# -20210715.net
KiCad netlist of a schematic drawn in Altium Designer
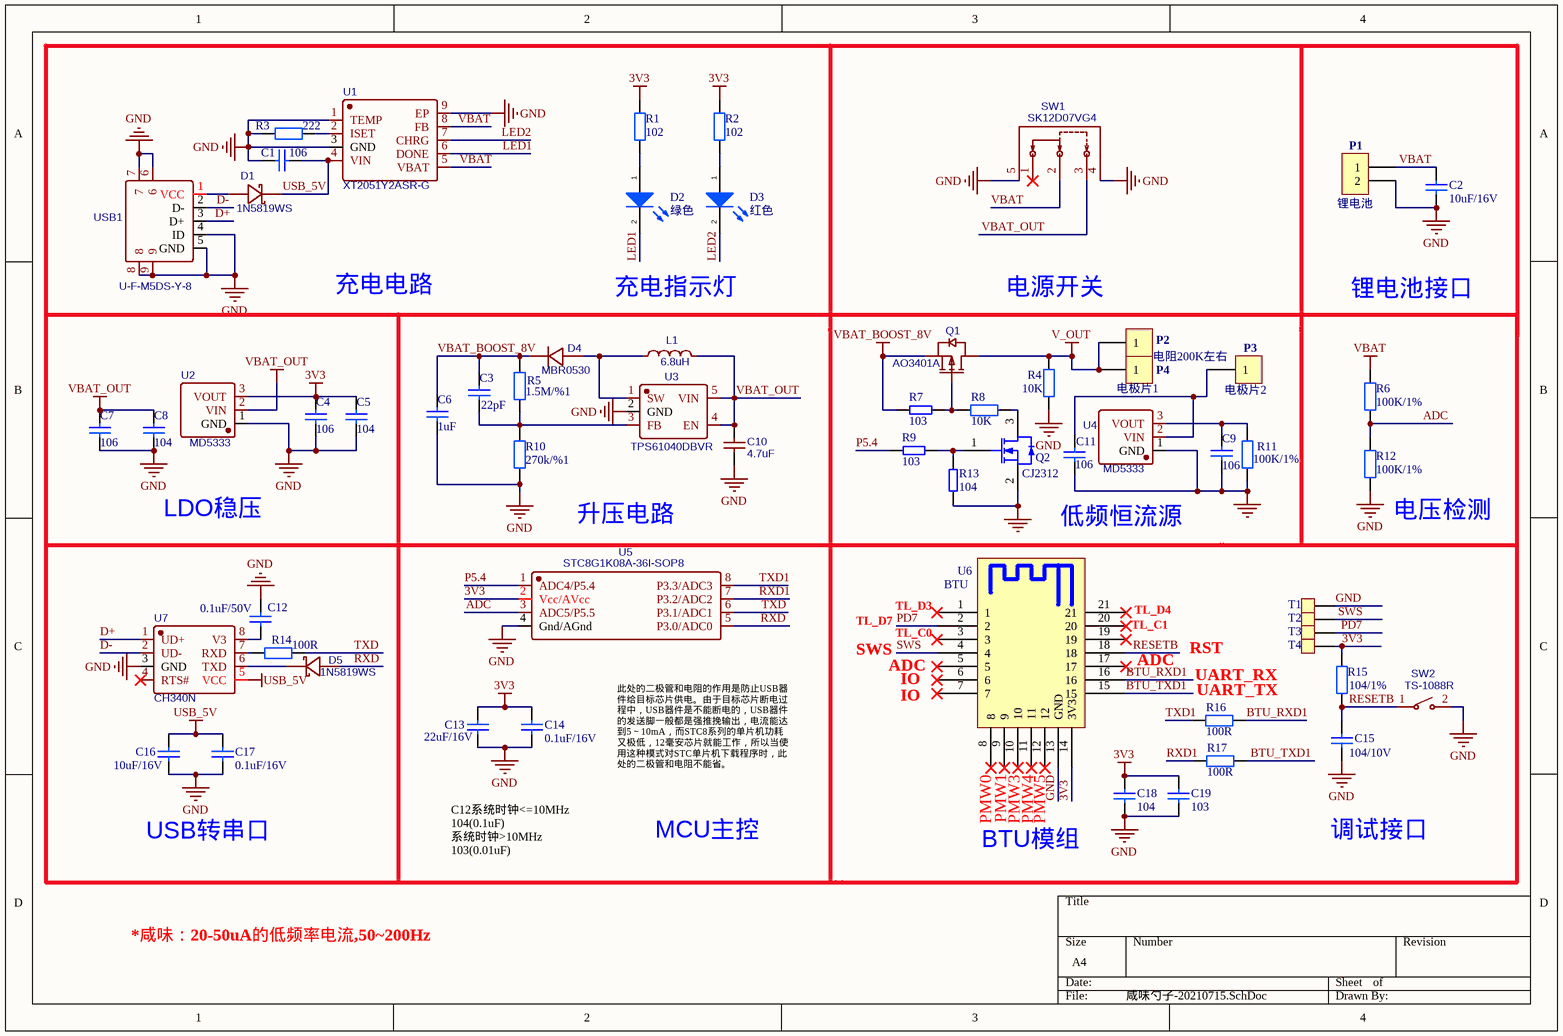
[diagram p0: 咸味勺子-20210715.SchDoc]

(export (version "E")
  (design (tool "Eeschema 10.0.6"))
  (components
    (comp (ref "C1")
      (value "106")
      (footprint "C0603")
      (description "无极性电容")
      (fields (field (name "PART NUMBER") "1.02.03.00181") (field (name "修改人") "system"))
      (libsource (lib "Database_Libs") (part "Capacitor - non polarized"))
    )
    (comp (ref "C2")
      (value "10uF/16V")
      (footprint "C0603")
      (description "无极性电容")
      (fields (field (name "PART NUMBER") "1.02.05.00869"))
      (libsource (lib "Database_Libs4") (part "Capacitor - non polarized"))
    )
    (comp (ref "C3")
      (value "22pF")
      (footprint "C0402_GRM15")
      (description "无极性电容")
      (fields (field (name "PART NUMBER") "1.02.05.00869"))
      (libsource (lib "Database_Libs4") (part "Capacitor - non polarized"))
    )
    (comp (ref "C4")
      (value "106")
      (footprint "C0603")
      (description "无极性电容")
      (fields (field (name "PART NUMBER") "1.02.05.00869"))
      (libsource (lib "Database_Libs4") (part "Capacitor - non polarized"))
    )
    (comp (ref "C5")
      (value "104")
      (footprint "C0402_GRM15")
      (description "无极性电容")
      (fields (field (name "PART NUMBER") "1.02.05.00869"))
      (libsource (lib "Database_Libs4") (part "Capacitor - non polarized"))
    )
    (comp (ref "C6")
      (value "1uF")
      (footprint "C0603")
      (description "无极性电容")
      (fields (field (name "PART NUMBER") "1.02.05.00869"))
      (libsource (lib "Database_Libs4") (part "Capacitor - non polarized"))
    )
    (comp (ref "C7")
      (value "106")
      (footprint "C0603")
      (description "无极性电容")
      (fields (field (name "PART NUMBER") "1.02.05.00869"))
      (libsource (lib "Database_Libs4") (part "Capacitor - non polarized"))
    )
    (comp (ref "C8")
      (value "104")
      (footprint "C0402_GRM15")
      (description "无极性电容")
      (fields (field (name "PART NUMBER") "1.02.05.00869"))
      (libsource (lib "Database_Libs4") (part "Capacitor - non polarized"))
    )
    (comp (ref "C9")
      (value "106")
      (footprint "C0603")
      (description "无极性电容")
      (fields (field (name "PART NUMBER") "1.02.05.00869"))
      (libsource (lib "Database_Libs4") (part "Capacitor - non polarized"))
    )
    (comp (ref "C10")
      (value "4.7uF")
      (footprint "JMK212BJ475KG-T")
      (fields
        (field (name "BOM_MANUFACTURER PART") "JMK212BJ475KG-T")
        (field (name "BOM_SUPPLIER PART") "C92788")
      )
      (libsource (lib "altium-import") (part "root_1_4.7uF_"))
    )
    (comp (ref "C11")
      (value "106")
      (footprint "C0603")
      (description "无极性电容")
      (fields (field (name "PART NUMBER") "1.02.05.00869"))
      (libsource (lib "Database_Libs4") (part "Capacitor - non polarized"))
    )
    (comp (ref "C12")
      (value "0.1uF/50V")
      (footprint "C0402_GRM15")
      (description "无极性电容")
      (fields (field (name "PART NUMBER") "1.02.05.00834") (field (name "修改人") "system"))
      (libsource (lib "Database_Libs") (part "Capacitor - non polarized"))
    )
    (comp (ref "C13")
      (value "22uF/16V")
      (footprint "C0603")
      (description "无极性电容")
      (fields (field (name "PART NUMBER") "1.02.03.00181") (field (name "修改人") "system"))
      (libsource (lib "Database_Libs") (part "Capacitor - non polarized"))
    )
    (comp (ref "C14")
      (value "0.1uF/16V")
      (footprint "C0402_GRM15")
      (description "无极性电容")
      (fields (field (name "PART NUMBER") "1.02.05.00834") (field (name "修改人") "system"))
      (libsource (lib "Database_Libs") (part "Capacitor - non polarized"))
    )
    (comp (ref "C15")
      (value "104/10V")
      (footprint "C0402_GRM15")
      (description "无极性电容")
      (fields (field (name "PART NUMBER") "1.02.05.00869"))
      (libsource (lib "Database_Libs4") (part "Capacitor - non polarized"))
    )
    (comp (ref "C16")
      (value "10uF/16V")
      (footprint "C0603")
      (description "无极性电容")
      (fields (field (name "PART NUMBER") "1.02.03.00181") (field (name "修改人") "system"))
      (libsource (lib "Database_Libs") (part "Capacitor - non polarized"))
    )
    (comp (ref "C17")
      (value "0.1uF/16V")
      (footprint "C0402_GRM15")
      (description "无极性电容")
      (fields (field (name "PART NUMBER") "1.02.05.00834") (field (name "修改人") "system"))
      (libsource (lib "Database_Libs") (part "Capacitor - non polarized"))
    )
    (comp (ref "C18")
      (value "104")
      (footprint "C0402_GRM15")
      (description "无极性电容")
      (fields (field (name "PART NUMBER") "1.02.05.00869"))
      (libsource (lib "Database_Libs4") (part "Capacitor - non polarized"))
    )
    (comp (ref "C19")
      (value "103")
      (footprint "C0402_GRM15")
      (description "无极性电容")
      (fields (field (name "PART NUMBER") "1.02.05.00869"))
      (libsource (lib "Database_Libs4") (part "Capacitor - non polarized"))
    )
    (comp (ref "D1")
      (value "1N5819WS")
      (footprint "1N5819WS")
      (fields (field (name "BOM_SUPPLIER PART") "C1884554") (field (name "CONTRIBUTOR") "LCSC"))
      (libsource (lib "altium-import") (part "root_2_1N5819WS_C1884554_"))
    )
    (comp (ref "D2")
      (value "绿色")
      (footprint "OSR50603C1E")
      (description "LED")
      (fields (field (name "PART NUMBER") "1.06.02.00452"))
      (libsource (lib "Database_Libs4") (part "LED"))
    )
    (comp (ref "D3")
      (value "红色")
      (footprint "OSR50603C1E")
      (description "LED")
      (fields (field (name "PART NUMBER") "1.06.02.00452"))
      (libsource (lib "Database_Libs4") (part "LED"))
    )
    (comp (ref "D4")
      (value "MBR0530")
      (footprint "MBR0530")
      (fields (field (name "BOM_SUPPLIER PART") "C475718") (field (name "CONTRIBUTOR") "LCSC"))
      (libsource (lib "altium-import") (part "root_0_MBR0530_C475718_"))
    )
    (comp (ref "D5")
      (value "1N5819WS")
      (footprint "1N5819WS")
      (fields (field (name "BOM_SUPPLIER PART") "C1884554") (field (name "CONTRIBUTOR") "LCSC"))
      (libsource (lib "altium-import") (part "root_0_1N5819WS_C1884554_"))
    )
    (comp (ref "L1")
      (value "6.8uH")
      (footprint "CDRH3D23NP-6R8PC")
      (fields
        (field (name "BOM_SUPPLIER PART") "C323532")
        (field (name "BOM_MANUFACTURER PART") "CDRH3D23NP-6R8PC")
        (field (name "CONTRIBUTOR") "LCSC")
      )
      (libsource (lib "altium-import") (part "root_0_6.8uH_"))
    )
    (comp (ref "P1")
      (value "锂电池")
      (footprint "1.5mm 2p接插件")
      (description "Connector")
      (libsource (lib "*") (part "CON2"))
    )
    (comp (ref "P2") (value "CON1") (footprint "焊点1") (libsource (lib "智能烧水壶 -电源板") (part "CON1")))
    (comp (ref "P3") (value "CON1") (footprint "焊点1") (libsource (lib "智能烧水壶 -电源板") (part "CON1")))
    (comp (ref "P4") (value "CON1") (footprint "焊点1") (libsource (lib "智能烧水壶 -电源板") (part "CON1")))
    (comp (ref "Q1")
      (value "AO3401A")
      (footprint "AO3401A")
      (fields (field (name "BOM_SUPPLIER PART") "C700954") (field (name "CONTRIBUTOR") "LCSC"))
      (libsource (lib "altium-import") (part "root_1_mirrored_AO3401A_C700954_"))
    )
    (comp (ref "Q2")
      (value "CJ2312")
      (footprint "CJ2312")
      (description "N-Channel MOSFET")
      (fields
        (field (name "PART NUMBER") "1.06.11.00008")
        (field (name "ORCAD LIBRARY PATH") "‪Z:\\tuya_lib\\sch-lib\\DISCRETE.OLB")
        (field (name "修改人") "system")
      )
      (libsource (lib "Database_Libs") (part "MOSFET-N"))
    )
    (comp (ref "R1")
      (value "102")
      (footprint "R0402")
      (description "电阻")
      (fields (field (name "PART NUMBER") "1.01.01.00808"))
      (libsource (lib "") (part "Resistor_1"))
    )
    (comp (ref "R2")
      (value "102")
      (footprint "R0402")
      (description "电阻")
      (fields (field (name "PART NUMBER") "1.01.01.00808"))
      (libsource (lib "") (part "Resistor_1"))
    )
    (comp (ref "R3")
      (value "222")
      (footprint "R0402")
      (description "电阻")
      (fields (field (name "PART NUMBER") "1.01.01.00808"))
      (libsource (lib "Database_Libs4") (part "Resistor"))
    )
    (comp (ref "R4")
      (value "10K")
      (footprint "R0402")
      (description "电阻")
      (libsource (lib "Database_Libs") (part "Resistor"))
    )
    (comp (ref "R5")
      (value "1.5M/%1")
      (footprint "R0402")
      (description "电阻")
      (libsource (lib "") (part "Resistor_1"))
    )
    (comp (ref "R6")
      (value "100K/1%")
      (footprint "R0402")
      (description "电阻")
      (libsource (lib "") (part "Resistor_1"))
    )
    (comp (ref "R7")
      (value "103")
      (footprint "R0402")
      (description "RES")
      (libsource (lib "先锋器件封装库") (part "RES-1"))
    )
    (comp (ref "R8")
      (value "10K")
      (footprint "R0402")
      (description "电阻")
      (libsource (lib "") (part "Resistor_2"))
    )
    (comp (ref "R9")
      (value "103")
      (footprint "R0402")
      (description "RES")
      (libsource (lib "先锋器件封装库") (part "RES-1"))
    )
    (comp (ref "R10")
      (value "270k/%1")
      (footprint "R0402")
      (description "电阻")
      (libsource (lib "") (part "Resistor_1"))
    )
    (comp (ref "R11")
      (value "100K/1%")
      (footprint "R0402")
      (description "电阻")
      (libsource (lib "") (part "Resistor_1"))
    )
    (comp (ref "R12")
      (value "100K/1%")
      (footprint "R0402")
      (description "电阻")
      (libsource (lib "") (part "Resistor_1"))
    )
    (comp (ref "R13")
      (value "104")
      (footprint "R0402")
      (description "RES")
      (libsource (lib "先锋器件封装库") (part "RES-1"))
    )
    (comp (ref "R14")
      (value "100R")
      (footprint "R0402")
      (description "电阻")
      (fields (field (name "PART NUMBER") "1.01.01.00808") (field (name "修改人") "system"))
      (libsource (lib "") (part "Resistor_2"))
    )
    (comp (ref "R15")
      (value "104/1%")
      (footprint "R0402")
      (description "电阻")
      (fields (field (name "PART NUMBER") "1.01.01.00808"))
      (libsource (lib "") (part "Resistor_1"))
    )
    (comp (ref "R16")
      (value "100R")
      (footprint "R0402")
      (description "电阻")
      (fields (field (name "PART NUMBER") "1.01.01.00808"))
      (libsource (lib "Database_Libs4") (part "Resistor"))
    )
    (comp (ref "R17")
      (value "100R")
      (footprint "R0402")
      (description "电阻")
      (fields (field (name "PART NUMBER") "1.01.01.00808"))
      (libsource (lib "Database_Libs4") (part "Resistor"))
    )
    (comp (ref "SW1")
      (value "SK12D07VG4")
      (footprint "SK12D07VG4")
      (fields (field (name "BOM_SUPPLIER PART") "C393937") (field (name "CONTRIBUTOR") "LCSC"))
      (libsource (lib "altium-import") (part "root_0_SK12D07VG4_"))
    )
    (comp (ref "SW2")
      (value "TS-1088R")
      (footprint "TS-1088R-02026")
      (fields
        (field (name "BOM_SUPPLIER PART") "C455280")
        (field (name "BOM_MANUFACTURER PART") "TS-1088R-02026")
        (field (name "CONTRIBUTOR") "LCSC")
      )
      (libsource (lib "altium-import") (part "root_0_TS-1088R-02026_"))
    )
    (comp (ref "T1") (value "TP") (footprint "TP1") (libsource (lib "MIAXIS-SCH") (part "TP")))
    (comp (ref "T2") (value "TP") (footprint "TP1") (libsource (lib "MIAXIS-SCH") (part "TP")))
    (comp (ref "T3") (value "TP") (footprint "TP1") (libsource (lib "MIAXIS-SCH") (part "TP")))
    (comp (ref "T4") (value "TP") (footprint "TP1") (libsource (lib "MIAXIS-SCH") (part "TP")))
    (comp (ref "U1")
      (value "XT2051Y2ASR-G")
      (footprint "XT2051Y2ASR-G")
      (fields (field (name "BOM_SUPPLIER PART") "C236398") (field (name "CONTRIBUTOR") "LCSC"))
      (libsource (lib "altium-import") (part "root_0_XT2051Y2ASR-G_"))
    )
    (comp (ref "U2")
      (value "MD5333")
      (footprint "MD5333")
      (fields (field (name "BOM_SUPPLIER PART") "C2827936") (field (name "CONTRIBUTOR") "LCSC"))
      (libsource (lib "altium-import") (part "root_2_MD5333_"))
    )
    (comp (ref "U3")
      (value "TPS61040DBVR")
      (footprint "TPS61040DBVR")
      (fields (field (name "BOM_SUPPLIER PART") "C7722"))
      (libsource (lib "altium-import") (part "root_0_TPS61040DBVR_"))
    )
    (comp (ref "U4")
      (value "MD5333")
      (footprint "MD5333")
      (fields (field (name "BOM_SUPPLIER PART") "C2827936") (field (name "CONTRIBUTOR") "LCSC"))
      (libsource (lib "altium-import") (part "root_2_MD5333_"))
    )
    (comp (ref "U5")
      (value "STC8G1K08A-36I-SOP8")
      (footprint "STC8G1K08A-36I-SOP8")
      (fields (field (name "BOM_SUPPLIER PART") "C915663") (field (name "CONTRIBUTOR") "LCSC"))
      (libsource (lib "altium-import") (part "root_0_STC8G1K08A-36I-SOP8_"))
    )
    (comp (ref "U6")
      (value "BTU")
      (footprint "CBU1")
      (fields (field (name "PART NUMBER") "0110"))
      (libsource (lib "BTU_V100") (part "CBU"))
    )
    (comp (ref "U7")
      (value "CH340N")
      (footprint "CH340N")
      (fields (field (name "BOM_SUPPLIER PART") "C506813") (field (name "CONTRIBUTOR") "LCSC"))
      (libsource (lib "TY") (part "CH340N"))
    )
    (comp (ref "USB1")
      (value "U-F-M5DS-Y-8")
      (footprint "U-F-M5DS-Y-8")
      (fields (field (name "BOM_SUPPLIER PART") "C961761") (field (name "CONTRIBUTOR") "LCSC"))
      (libsource (lib "altium-import") (part "root_0_U-F-M5DS-Y-8_"))
    )
  )
  (nets
    (net (code "1") (name "/ADC") (class "Default")
      (node (ref "R12") (pin "2") (pinfunction "2_2") (pintype "passive"))
      (node (ref "R6") (pin "1") (pinfunction "1_1") (pintype "passive"))
      (node (ref "U5") (pin "3") (pinfunction "ADC5/P5.5_3") (pintype "passive"))
    )
    (net (code "2") (name "/BTU_RXD1") (class "Default")
      (node (ref "R16") (pin "1") (pinfunction "1_1") (pintype "passive"))
      (node (ref "U6") (pin "16") (pinfunction "16_16") (pintype "passive"))
    )
    (net (code "3") (name "/BTU_TXD1") (class "Default")
      (node (ref "R17") (pin "1") (pinfunction "1_1") (pintype "passive"))
      (node (ref "U6") (pin "15") (pinfunction "15_15") (pintype "passive"))
    )
    (net (code "4") (name "/D+") (class "Default")
      (node (ref "U7") (pin "1") (pinfunction "UD+_1") (pintype "passive"))
      (node (ref "USB1") (pin "3") (pinfunction "D+_3") (pintype "passive"))
    )
    (net (code "5") (name "/D-") (class "Default")
      (node (ref "U7") (pin "2") (pinfunction "UD-_2") (pintype "passive"))
      (node (ref "USB1") (pin "2") (pinfunction "D-_2") (pintype "passive"))
    )
    (net (code "6") (name "/LED1") (class "Default")
      (node (ref "D2") (pin "2") (pinfunction "2_2") (pintype "passive"))
      (node (ref "U1") (pin "6") (pinfunction "DONE_6") (pintype "passive"))
    )
    (net (code "7") (name "/LED2") (class "Default")
      (node (ref "D3") (pin "2") (pinfunction "2_2") (pintype "passive"))
      (node (ref "U1") (pin "7") (pinfunction "CHRG_7") (pintype "passive"))
    )
    (net (code "8") (name "/P5.4") (class "Default")
      (node (ref "R9") (pin "1") (pintype "passive"))
      (node (ref "U5") (pin "1") (pinfunction "ADC4/P5.4_1") (pintype "passive"))
    )
    (net (code "9") (name "/PD7") (class "Default")
      (node (ref "T3") (pin "1") (pinfunction "1_1") (pintype "passive"))
      (node (ref "U6") (pin "2") (pinfunction "2_2") (pintype "passive"))
    )
    (net (code "10") (name "/RESETB") (class "Default")
      (node (ref "C15") (pin "1") (pinfunction "1_1") (pintype "passive"))
      (node (ref "R15") (pin "1") (pinfunction "1_1") (pintype "passive"))
      (node (ref "SW2") (pin "1") (pinfunction "1_1") (pintype "passive"))
      (node (ref "U6") (pin "18") (pinfunction "18_18") (pintype "passive"))
    )
    (net (code "11") (name "/RXD") (class "Default")
      (node (ref "D5") (pin "2") (pinfunction "A_2") (pintype "passive"))
      (node (ref "U5") (pin "5") (pinfunction "P3.0/ADC0_5") (pintype "passive"))
    )
    (net (code "12") (name "/RXD1") (class "Default")
      (node (ref "R17") (pin "2") (pinfunction "2_2") (pintype "passive"))
      (node (ref "U5") (pin "7") (pinfunction "P3.2/ADC2_7") (pintype "passive"))
    )
    (net (code "13") (name "/SWS") (class "Default")
      (node (ref "T2") (pin "1") (pinfunction "1_1") (pintype "passive"))
      (node (ref "U6") (pin "4") (pinfunction "4_4") (pintype "passive"))
    )
    (net (code "14") (name "/TXD") (class "Default")
      (node (ref "R14") (pin "2") (pinfunction "2_2") (pintype "passive"))
      (node (ref "U5") (pin "6") (pinfunction "P3.1/ADC1_6") (pintype "passive"))
    )
    (net (code "15") (name "/TXD1") (class "Default")
      (node (ref "R16") (pin "2") (pinfunction "2_2") (pintype "passive"))
      (node (ref "U5") (pin "8") (pinfunction "P3.3/ADC3_8") (pintype "passive"))
    )
    (net (code "16") (name "3V3") (class "Default")
      (node (ref "C13") (pin "2") (pinfunction "2_2") (pintype "passive"))
      (node (ref "C14") (pin "2") (pinfunction "2_2") (pintype "passive"))
      (node (ref "C18") (pin "1") (pinfunction "1_1") (pintype "passive"))
      (node (ref "C19") (pin "1") (pinfunction "1_1") (pintype "passive"))
      (node (ref "C4") (pin "1") (pinfunction "1_1") (pintype "passive"))
      (node (ref "C5") (pin "1") (pinfunction "1_1") (pintype "passive"))
      (node (ref "R1") (pin "2") (pinfunction "2_2") (pintype "passive"))
      (node (ref "R15") (pin "2") (pinfunction "2_2") (pintype "passive"))
      (node (ref "R2") (pin "2") (pinfunction "2_2") (pintype "passive"))
      (node (ref "T4") (pin "1") (pinfunction "1_1") (pintype "passive"))
      (node (ref "U2") (pin "3") (pinfunction "VOUT_3") (pintype "passive"))
      (node (ref "U5") (pin "2") (pinfunction "Vcc/AVcc_2") (pintype "passive"))
      (node (ref "U6") (pin "14") (pinfunction "3V3_14") (pintype "passive"))
    )
    (net (code "17") (name "GND") (class "Default")
      (node (ref "C1") (pin "2") (pinfunction "2_2") (pintype "passive"))
      (node (ref "C10") (pin "1") (pinfunction "1_1") (pintype "passive"))
      (node (ref "C11") (pin "2") (pinfunction "2_2") (pintype "passive"))
      (node (ref "C12") (pin "2") (pinfunction "2_2") (pintype "passive"))
      (node (ref "C13") (pin "1") (pinfunction "1_1") (pintype "passive"))
      (node (ref "C14") (pin "1") (pinfunction "1_1") (pintype "passive"))
      (node (ref "C15") (pin "2") (pinfunction "2_2") (pintype "passive"))
      (node (ref "C16") (pin "1") (pinfunction "1_1") (pintype "passive"))
      (node (ref "C17") (pin "1") (pinfunction "1_1") (pintype "passive"))
      (node (ref "C18") (pin "2") (pinfunction "2_2") (pintype "passive"))
      (node (ref "C19") (pin "2") (pinfunction "2_2") (pintype "passive"))
      (node (ref "C2") (pin "2") (pinfunction "2_2") (pintype "passive"))
      (node (ref "C4") (pin "2") (pinfunction "2_2") (pintype "passive"))
      (node (ref "C5") (pin "2") (pinfunction "2_2") (pintype "passive"))
      (node (ref "C6") (pin "2") (pinfunction "2_2") (pintype "passive"))
      (node (ref "C7") (pin "2") (pinfunction "2_2") (pintype "passive"))
      (node (ref "C8") (pin "2") (pinfunction "2_2") (pintype "passive"))
      (node (ref "C9") (pin "2") (pinfunction "2_2") (pintype "passive"))
      (node (ref "P1") (pin "2") (pinfunction "2_2") (pintype "passive"))
      (node (ref "Q2") (pin "2") (pinfunction "S_2") (pintype "passive"))
      (node (ref "R10") (pin "1") (pinfunction "1_1") (pintype "passive"))
      (node (ref "R11") (pin "1") (pinfunction "1_1") (pintype "passive"))
      (node (ref "R12") (pin "1") (pinfunction "1_1") (pintype "passive"))
      (node (ref "R13") (pin "1") (pintype "passive"))
      (node (ref "R3") (pin "2") (pinfunction "2_2") (pintype "passive"))
      (node (ref "R4") (pin "2") (pinfunction "2_2") (pintype "passive"))
      (node (ref "SW1") (pin "4") (pinfunction "4_4") (pintype "passive"))
      (node (ref "SW1") (pin "5") (pinfunction "5_5") (pintype "passive"))
      (node (ref "SW2") (pin "2") (pinfunction "2_2") (pintype "passive"))
      (node (ref "T1") (pin "1") (pinfunction "1_1") (pintype "passive"))
      (node (ref "U1") (pin "1") (pinfunction "TEMP_1") (pintype "passive"))
      (node (ref "U1") (pin "3") (pinfunction "GND_3") (pintype "passive"))
      (node (ref "U1") (pin "9") (pinfunction "EP_9") (pintype "passive"))
      (node (ref "U2") (pin "1") (pinfunction "GND_1") (pintype "passive"))
      (node (ref "U3") (pin "2") (pinfunction "GND_2") (pintype "passive"))
      (node (ref "U4") (pin "1") (pinfunction "GND_1") (pintype "passive"))
      (node (ref "U5") (pin "4") (pinfunction "Gnd/AGnd_4") (pintype "passive"))
      (node (ref "U6") (pin "13") (pinfunction "GND_13") (pintype "passive"))
      (node (ref "U7") (pin "3") (pinfunction "GND_3") (pintype "passive"))
      (node (ref "USB1") (pin "4") (pinfunction "ID_4") (pintype "passive"))
      (node (ref "USB1") (pin "5") (pinfunction "GND_5") (pintype "passive"))
      (node (ref "USB1") (pin "6") (pinfunction "6_6") (pintype "passive"))
      (node (ref "USB1") (pin "7") (pinfunction "7_7") (pintype "passive"))
      (node (ref "USB1") (pin "8") (pinfunction "8_8") (pintype "passive"))
      (node (ref "USB1") (pin "9") (pinfunction "9_9") (pintype "passive"))
    )
    (net (code "18") (name "Net-(D1-A)") (class "Default")
      (node (ref "D1") (pin "2") (pinfunction "A_2") (pintype "passive"))
      (node (ref "USB1") (pin "1") (pinfunction "VCC_1") (pintype "passive"))
    )
    (net (code "19") (name "Net-(D2-Pad1)") (class "Default")
      (node (ref "D2") (pin "1") (pinfunction "1_1") (pintype "passive"))
      (node (ref "R1") (pin "1") (pinfunction "1_1") (pintype "passive"))
    )
    (net (code "20") (name "Net-(D3-Pad1)") (class "Default")
      (node (ref "D3") (pin "1") (pinfunction "1_1") (pintype "passive"))
      (node (ref "R2") (pin "1") (pinfunction "1_1") (pintype "passive"))
    )
    (net (code "21") (name "Net-(D4-A)") (class "Default")
      (node (ref "D4") (pin "2") (pinfunction "A_2") (pintype "passive"))
      (node (ref "L1") (pin "1") (pinfunction "1_1") (pintype "passive"))
      (node (ref "U3") (pin "1") (pinfunction "SW_1") (pintype "passive"))
    )
    (net (code "22") (name "Net-(D5-C)") (class "Default")
      (node (ref "D5") (pin "1") (pinfunction "C_1") (pintype "passive"))
      (node (ref "U7") (pin "6") (pinfunction "TXD_6") (pintype "passive"))
    )
    (net (code "23") (name "Net-(Q1-G)") (class "Default")
      (node (ref "Q1") (pin "1") (pinfunction "G_1") (pintype "passive"))
      (node (ref "R7") (pin "2") (pintype "passive"))
      (node (ref "R8") (pin "1") (pinfunction "1_1") (pintype "passive"))
    )
    (net (code "24") (name "Net-(Q2-D)") (class "Default")
      (node (ref "Q2") (pin "3") (pinfunction "D_3") (pintype "passive"))
      (node (ref "R8") (pin "2") (pinfunction "2_2") (pintype "passive"))
    )
    (net (code "25") (name "Net-(Q2-G)") (class "Default")
      (node (ref "Q2") (pin "1") (pinfunction "G_1") (pintype "passive"))
      (node (ref "R13") (pin "2") (pintype "passive"))
      (node (ref "R9") (pin "2") (pintype "passive"))
    )
    (net (code "26") (name "Net-(U1-ISET)") (class "Default")
      (node (ref "R3") (pin "1") (pinfunction "1_1") (pintype "passive"))
      (node (ref "U1") (pin "2") (pinfunction "ISET_2") (pintype "passive"))
    )
    (net (code "27") (name "Net-(U3-FB)") (class "Default")
      (node (ref "C3") (pin "2") (pinfunction "2_2") (pintype "passive"))
      (node (ref "R10") (pin "2") (pinfunction "2_2") (pintype "passive"))
      (node (ref "R5") (pin "1") (pinfunction "1_1") (pintype "passive"))
      (node (ref "U3") (pin "3") (pinfunction "FB_3") (pintype "passive"))
    )
    (net (code "28") (name "Net-(U4-VIN)") (class "Default")
      (node (ref "C11") (pin "1") (pinfunction "1_1") (pintype "passive"))
      (node (ref "P3") (pin "1") (pinfunction "1_1") (pintype "passive"))
      (node (ref "U4") (pin "2") (pinfunction "VIN_2") (pintype "passive"))
    )
    (net (code "29") (name "Net-(U4-VOUT)") (class "Default")
      (node (ref "C9") (pin "1") (pinfunction "1_1") (pintype "passive"))
      (node (ref "R11") (pin "2") (pinfunction "2_2") (pintype "passive"))
      (node (ref "U4") (pin "3") (pinfunction "VOUT_3") (pintype "passive"))
    )
    (net (code "30") (name "Net-(U7-RXD)") (class "Default")
      (node (ref "R14") (pin "1") (pinfunction "1_1") (pintype "passive"))
      (node (ref "U7") (pin "7") (pinfunction "RXD_7") (pintype "passive"))
    )
    (net (code "31") (name "Net-(U7-V3)") (class "Default")
      (node (ref "C12") (pin "1") (pinfunction "1_1") (pintype "passive"))
      (node (ref "U7") (pin "8") (pinfunction "V3_8") (pintype "passive"))
    )
    (net (code "32") (name "USB_5V") (class "Default")
      (node (ref "C1") (pin "1") (pinfunction "1_1") (pintype "passive"))
      (node (ref "C16") (pin "2") (pinfunction "2_2") (pintype "passive"))
      (node (ref "C17") (pin "2") (pinfunction "2_2") (pintype "passive"))
      (node (ref "D1") (pin "1") (pinfunction "C_1") (pintype "passive"))
      (node (ref "U1") (pin "4") (pinfunction "VIN_4") (pintype "passive"))
      (node (ref "U7") (pin "5") (pinfunction "VCC_5") (pintype "passive"))
    )
    (net (code "33") (name "VBAT") (class "Default")
      (node (ref "C2") (pin "1") (pinfunction "1_1") (pintype "passive"))
      (node (ref "P1") (pin "1") (pinfunction "1_1") (pintype "passive"))
      (node (ref "R6") (pin "2") (pinfunction "2_2") (pintype "passive"))
      (node (ref "SW1") (pin "2") (pinfunction "2_2") (pintype "passive"))
      (node (ref "U1") (pin "5") (pinfunction "VBAT_5") (pintype "passive"))
      (node (ref "U1") (pin "8") (pinfunction "FB_8") (pintype "passive"))
    )
    (net (code "34") (name "VBAT_BOOST_8V") (class "Default")
      (node (ref "C3") (pin "1") (pinfunction "1_1") (pintype "passive"))
      (node (ref "C6") (pin "1") (pinfunction "1_1") (pintype "passive"))
      (node (ref "D4") (pin "1") (pinfunction "K_1") (pintype "passive"))
      (node (ref "Q1") (pin "2") (pinfunction "S_2") (pintype "passive"))
      (node (ref "R5") (pin "2") (pinfunction "2_2") (pintype "passive"))
      (node (ref "R7") (pin "1") (pintype "passive"))
    )
    (net (code "35") (name "VBAT_OUT") (class "Default")
      (node (ref "C10") (pin "2") (pinfunction "2_2") (pintype "passive"))
      (node (ref "C7") (pin "1") (pinfunction "1_1") (pintype "passive"))
      (node (ref "C8") (pin "1") (pinfunction "1_1") (pintype "passive"))
      (node (ref "L1") (pin "2") (pinfunction "2_2") (pintype "passive"))
      (node (ref "SW1") (pin "3") (pinfunction "3_3") (pintype "passive"))
      (node (ref "U2") (pin "2") (pinfunction "VIN_2") (pintype "passive"))
      (node (ref "U3") (pin "4") (pinfunction "EN_4") (pintype "passive"))
      (node (ref "U3") (pin "5") (pinfunction "VIN_5") (pintype "passive"))
    )
    (net (code "36") (name "V_OUT") (class "Default")
      (node (ref "P2") (pin "1") (pinfunction "1_1") (pintype "passive"))
      (node (ref "P4") (pin "1") (pinfunction "1_1") (pintype "passive"))
      (node (ref "Q1") (pin "3") (pinfunction "D_3") (pintype "passive"))
      (node (ref "R4") (pin "1") (pinfunction "1_1") (pintype "passive"))
    )
    (net (code "37") (name "unconnected-(SW1-Pad1)") (class "Default")
      (node (ref "SW1") (pin "1") (pinfunction "1_1") (pintype "passive+no_connect"))
    )
    (net (code "38") (name "unconnected-(U6-Pad1)") (class "Default")
      (node (ref "U6") (pin "1") (pinfunction "1_1") (pintype "passive+no_connect"))
    )
    (net (code "39") (name "unconnected-(U6-Pad3)") (class "Default")
      (node (ref "U6") (pin "3") (pinfunction "3_3") (pintype "passive+no_connect"))
    )
    (net (code "40") (name "unconnected-(U6-Pad5)") (class "Default")
      (node (ref "U6") (pin "5") (pinfunction "5_5") (pintype "passive+no_connect"))
    )
    (net (code "41") (name "unconnected-(U6-Pad6)") (class "Default")
      (node (ref "U6") (pin "6") (pinfunction "6_6") (pintype "passive+no_connect"))
    )
    (net (code "42") (name "unconnected-(U6-Pad7)") (class "Default")
      (node (ref "U6") (pin "7") (pinfunction "7_7") (pintype "passive+no_connect"))
    )
    (net (code "43") (name "unconnected-(U6-Pad8)") (class "Default")
      (node (ref "U6") (pin "8") (pinfunction "8_8") (pintype "passive+no_connect"))
    )
    (net (code "44") (name "unconnected-(U6-Pad9)") (class "Default")
      (node (ref "U6") (pin "9") (pinfunction "9_9") (pintype "passive+no_connect"))
    )
    (net (code "45") (name "unconnected-(U6-Pad10)") (class "Default")
      (node (ref "U6") (pin "10") (pinfunction "10_10") (pintype "passive+no_connect"))
    )
    (net (code "46") (name "unconnected-(U6-Pad11)") (class "Default")
      (node (ref "U6") (pin "11") (pinfunction "11_11") (pintype "passive+no_connect"))
    )
    (net (code "47") (name "unconnected-(U6-Pad12)") (class "Default")
      (node (ref "U6") (pin "12") (pinfunction "12_12") (pintype "passive+no_connect"))
    )
    (net (code "48") (name "unconnected-(U6-Pad17)") (class "Default")
      (node (ref "U6") (pin "17") (pinfunction "17_17") (pintype "passive+no_connect"))
    )
    (net (code "49") (name "unconnected-(U6-Pad19)") (class "Default")
      (node (ref "U6") (pin "19") (pinfunction "19_19") (pintype "passive+no_connect"))
    )
    (net (code "50") (name "unconnected-(U6-Pad20)") (class "Default")
      (node (ref "U6") (pin "20") (pinfunction "20_20") (pintype "passive+no_connect"))
    )
    (net (code "51") (name "unconnected-(U6-Pad21)") (class "Default")
      (node (ref "U6") (pin "21") (pinfunction "21_21") (pintype "passive+no_connect"))
    )
    (net (code "52") (name "unconnected-(U7-RTS#-Pad4)") (class "Default")
      (node (ref "U7") (pin "4") (pinfunction "RTS#_4") (pintype "passive+no_connect"))
    )
  )
)
